# Magnetometer.net
KiCad netlist of a schematic drawn in Altium Designer
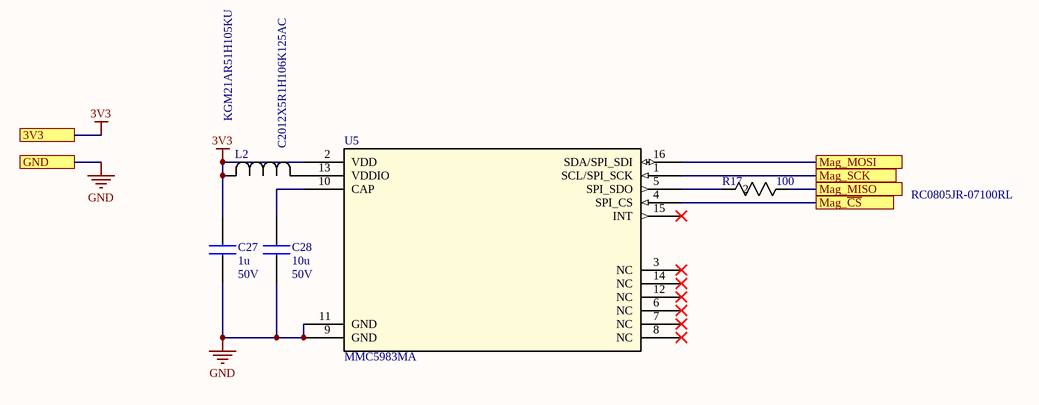
[diagram p0: Magnetometer.SchDoc]

(export (version "E")
  (design (tool "Eeschema 10.0.6"))
  (components
    (comp (ref "C27")
      (value "KGM21AR51H105KU")
      (footprint "CAPC2012X145N")
      (description "Multilayer Ceramic Chip Capacitors, Capacitance=1u")
      (fields (field (name "RATED VOLTAGE") "50V") (field (name "ALTIUM_VALUE") "1u"))
      (libsource (lib "Caps") (part "KGM21AR51H105KU"))
    )
    (comp (ref "C28")
      (value "C2012X5R1H106K125AC")
      (footprint "CAPC2012X145N")
      (description "Multilayer Ceramic Chip Capacitors, Capacitance=10?F, LxWxT:2x1.25x1.25mm")
      (fields
        (field (name "MOUSER PART NUMBER") "810-C2012X5R1H106K12")
        (field (name "RATED VOLTAGE") "50V")
        (field (name "ALTIUM_VALUE") "10u")
      )
      (libsource (lib "Caps") (part "C2012X5R1H106K125AC"))
    )
    (comp (ref "L2")
      (value "MPZ2012S601AT000")
      (footprint "IND_2012_TDK")
      (description "No Description Available")
      (fields (field (name "COPYRIGHT") "Copyright (C) 2025 Ultra Librarian. All rights reserved."))
      (libsource (lib "MPZ2012S601AT000") (part "MPZ2012S601AT000"))
    )
    (comp (ref "R17")
      (value "RC0805JR-07100RL")
      (footprint "RC0805N_YAG")
      (description "RES 0805 100 5% 1/8W")
      (fields (field (name "TOLERANCE") "5%") (field (name "ALTIUM_VALUE") "100"))
      (libsource (lib "Resistors") (part "RC0805JR-07100RL"))
    )
    (comp (ref "U5")
      (value "MMC5983MA")
      (footprint "MMC5983MA_MEM")
      (description "No Description Available")
      (fields (field (name "COPYRIGHT") "Copyright (C) 2025 Ultra Librarian. All rights reserved."))
      (libsource (lib "MMC5983MA") (part "MMC5983MA"))
    )
  )
  (nets
    (net (code "1") (name "/Mag_MISO") (class "Default")
      (node (ref "R17") (pin "1") (pinfunction "1_1") (pintype "passive"))
    )
    (net (code "2") (name "/Mag_MOSI") (class "Default")
      (node (ref "U5") (pin "16") (pinfunction "SDA/SPI_SDI_16") (pintype "bidirectional"))
    )
    (net (code "3") (name "/Mag_SCK") (class "Default")
      (node (ref "U5") (pin "1") (pinfunction "SCL/SPI_SCK_1") (pintype "input"))
    )
    (net (code "4") (name "/Mag_~{CS}") (class "Default")
      (node (ref "U5") (pin "4") (pinfunction "SPI_CS_4") (pintype "input"))
    )
    (net (code "5") (name "3V3") (class "Default")
      (node (ref "C27") (pin "2") (pinfunction "2_2") (pintype "passive"))
      (node (ref "L2") (pin "2") (pinfunction "2_2") (pintype "passive"))
      (node (ref "U5") (pin "2") (pinfunction "VDD_2") (pintype "power_in"))
    )
    (net (code "6") (name "GND") (class "Default")
      (node (ref "C27") (pin "1") (pinfunction "1_1") (pintype "passive"))
      (node (ref "C28") (pin "1") (pinfunction "1_1") (pintype "passive"))
      (node (ref "U5") (pin "11") (pinfunction "GND_11") (pintype "power_in"))
      (node (ref "U5") (pin "9") (pinfunction "GND_9") (pintype "power_in"))
    )
    (net (code "7") (name "Net-(U5-CAP)") (class "Default")
      (node (ref "C28") (pin "2") (pinfunction "2_2") (pintype "passive"))
      (node (ref "U5") (pin "10") (pinfunction "CAP_10") (pintype "power_in"))
    )
    (net (code "8") (name "Net-(U5-SPI_SDO)") (class "Default")
      (node (ref "R17") (pin "2") (pinfunction "2_2") (pintype "passive"))
      (node (ref "U5") (pin "5") (pinfunction "SPI_SDO_5") (pintype "output"))
    )
    (net (code "9") (name "Net-(U5-VDDIO)") (class "Default")
      (node (ref "L2") (pin "1") (pinfunction "1_1") (pintype "passive"))
      (node (ref "U5") (pin "13") (pinfunction "VDDIO_13") (pintype "power_in"))
    )
    (net (code "10") (name "unconnected-(U5-INT-Pad15)") (class "Default")
      (node (ref "U5") (pin "15") (pinfunction "INT_15") (pintype "output+no_connect"))
    )
    (net (code "11") (name "unconnected-(U5-NC-Pad3)") (class "Default")
      (node (ref "U5") (pin "3") (pinfunction "NC_3") (pintype "passive+no_connect"))
    )
    (net (code "12") (name "unconnected-(U5-NC-Pad6)") (class "Default")
      (node (ref "U5") (pin "6") (pinfunction "NC_6") (pintype "passive+no_connect"))
    )
    (net (code "13") (name "unconnected-(U5-NC-Pad7)") (class "Default")
      (node (ref "U5") (pin "7") (pinfunction "NC_7") (pintype "passive+no_connect"))
    )
    (net (code "14") (name "unconnected-(U5-NC-Pad8)") (class "Default")
      (node (ref "U5") (pin "8") (pinfunction "NC_8") (pintype "passive+no_connect"))
    )
    (net (code "15") (name "unconnected-(U5-NC-Pad12)") (class "Default")
      (node (ref "U5") (pin "12") (pinfunction "NC_12") (pintype "passive+no_connect"))
    )
    (net (code "16") (name "unconnected-(U5-NC-Pad14)") (class "Default")
      (node (ref "U5") (pin "14") (pinfunction "NC_14") (pintype "passive+no_connect"))
    )
  )
)
